# DS1307.net
KiCad netlist of a schematic drawn in Altium Designer
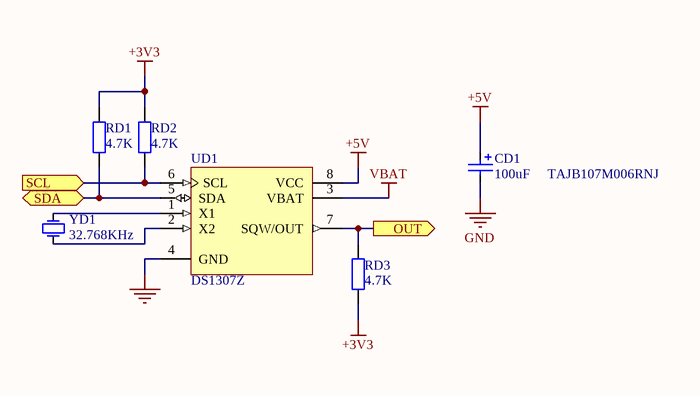
[diagram p0: DS1307.SchDoc]

(export (version "E")
  (design (tool "Eeschema 10.0.6"))
  (components
    (comp (ref "CD1")
      (value "100uF     TAJB107M006RNJ")
      (footprint "CAP_TAN_B_3518")
      (description "Capacitor")
      (fields (field (name "Comment") "Cap_Tan"))
      (libsource (lib "Peace的集成库") (part "Cap_Tan"))
    )
    (comp (ref "RD1")
      (value "4.7K")
      (footprint "RESC1608N")
      (description "Resistor")
      (fields (field (name "Comment") "Res1") (field (name "PUBLISHER") "Altium Limited"))
      (libsource (lib "Peace的集成库") (part "Res1"))
    )
    (comp (ref "RD2")
      (value "4.7K")
      (footprint "RESC1608N")
      (description "Resistor")
      (fields (field (name "Comment") "Res1") (field (name "PUBLISHER") "Altium Limited"))
      (libsource (lib "Peace的集成库") (part "Res1"))
    )
    (comp (ref "RD3")
      (value "4.7K")
      (footprint "RESC1608N")
      (description "Resistor")
      (fields (field (name "Comment") "Res1") (field (name "PUBLISHER") "Altium Limited"))
      (libsource (lib "Peace的集成库") (part "Res1"))
    )
    (comp (ref "UD1")
      (value "DS1307Z")
      (footprint "SOIC8_L")
      (description "64 X 8 Serial Real-Time Clock")
      (fields (field (name "PUBLISHER") "Altium Limited"))
      (libsource (lib "Peace的集成库") (part "DS1307Z"))
    )
    (comp (ref "YD1")
      (value "32.768KHz")
      (footprint "XTAL-206")
      (description "Crystal Oscillator")
      (fields (field (name "PUBLISHER") "Altium Limited"))
      (libsource (lib "Peace的集成库") (part "XTAL"))
    )
  )
  (nets
    (net (code "1") (name "+3V3") (class "Default")
      (node (ref "RD1") (pin "2") (pinfunction "2_2") (pintype "passive"))
      (node (ref "RD2") (pin "2") (pinfunction "2_2") (pintype "passive"))
      (node (ref "RD3") (pin "1") (pinfunction "1_1") (pintype "passive"))
    )
    (net (code "2") (name "+5V") (class "Default")
      (node (ref "CD1") (pin "1") (pinfunction "1_1") (pintype "passive"))
      (node (ref "UD1") (pin "8") (pinfunction "VCC_8") (pintype "power_in"))
    )
    (net (code "3") (name "/OUT") (class "Default")
      (node (ref "RD3") (pin "2") (pinfunction "2_2") (pintype "passive"))
      (node (ref "UD1") (pin "7") (pinfunction "SQW/OUT_7") (pintype "output"))
    )
    (net (code "4") (name "/SCL") (class "Default")
      (node (ref "RD2") (pin "1") (pinfunction "1_1") (pintype "passive"))
      (node (ref "UD1") (pin "6") (pinfunction "SCL_6") (pintype "input"))
    )
    (net (code "5") (name "/SDA") (class "Default")
      (node (ref "RD1") (pin "1") (pinfunction "1_1") (pintype "passive"))
      (node (ref "UD1") (pin "5") (pinfunction "SDA_5") (pintype "bidirectional"))
    )
    (net (code "6") (name "GND") (class "Default")
      (node (ref "CD1") (pin "2") (pinfunction "2_2") (pintype "passive"))
      (node (ref "UD1") (pin "4") (pinfunction "GND_4") (pintype "power_in"))
    )
    (net (code "7") (name "Net-(UD1-X1)") (class "Default")
      (node (ref "UD1") (pin "1") (pinfunction "X1_1") (pintype "input"))
      (node (ref "YD1") (pin "2") (pinfunction "OSC2_2") (pintype "passive"))
    )
    (net (code "8") (name "Net-(UD1-X2)") (class "Default")
      (node (ref "UD1") (pin "2") (pinfunction "X2_2") (pintype "input"))
      (node (ref "YD1") (pin "1") (pinfunction "OSC1_1") (pintype "passive"))
    )
    (net (code "9") (name "VBAT") (class "Default")
      (node (ref "UD1") (pin "3") (pinfunction "VBAT_3") (pintype "power_in"))
    )
  )
)
